# console_v2.net
KiCad netlist of a schematic drawn in EAGLE
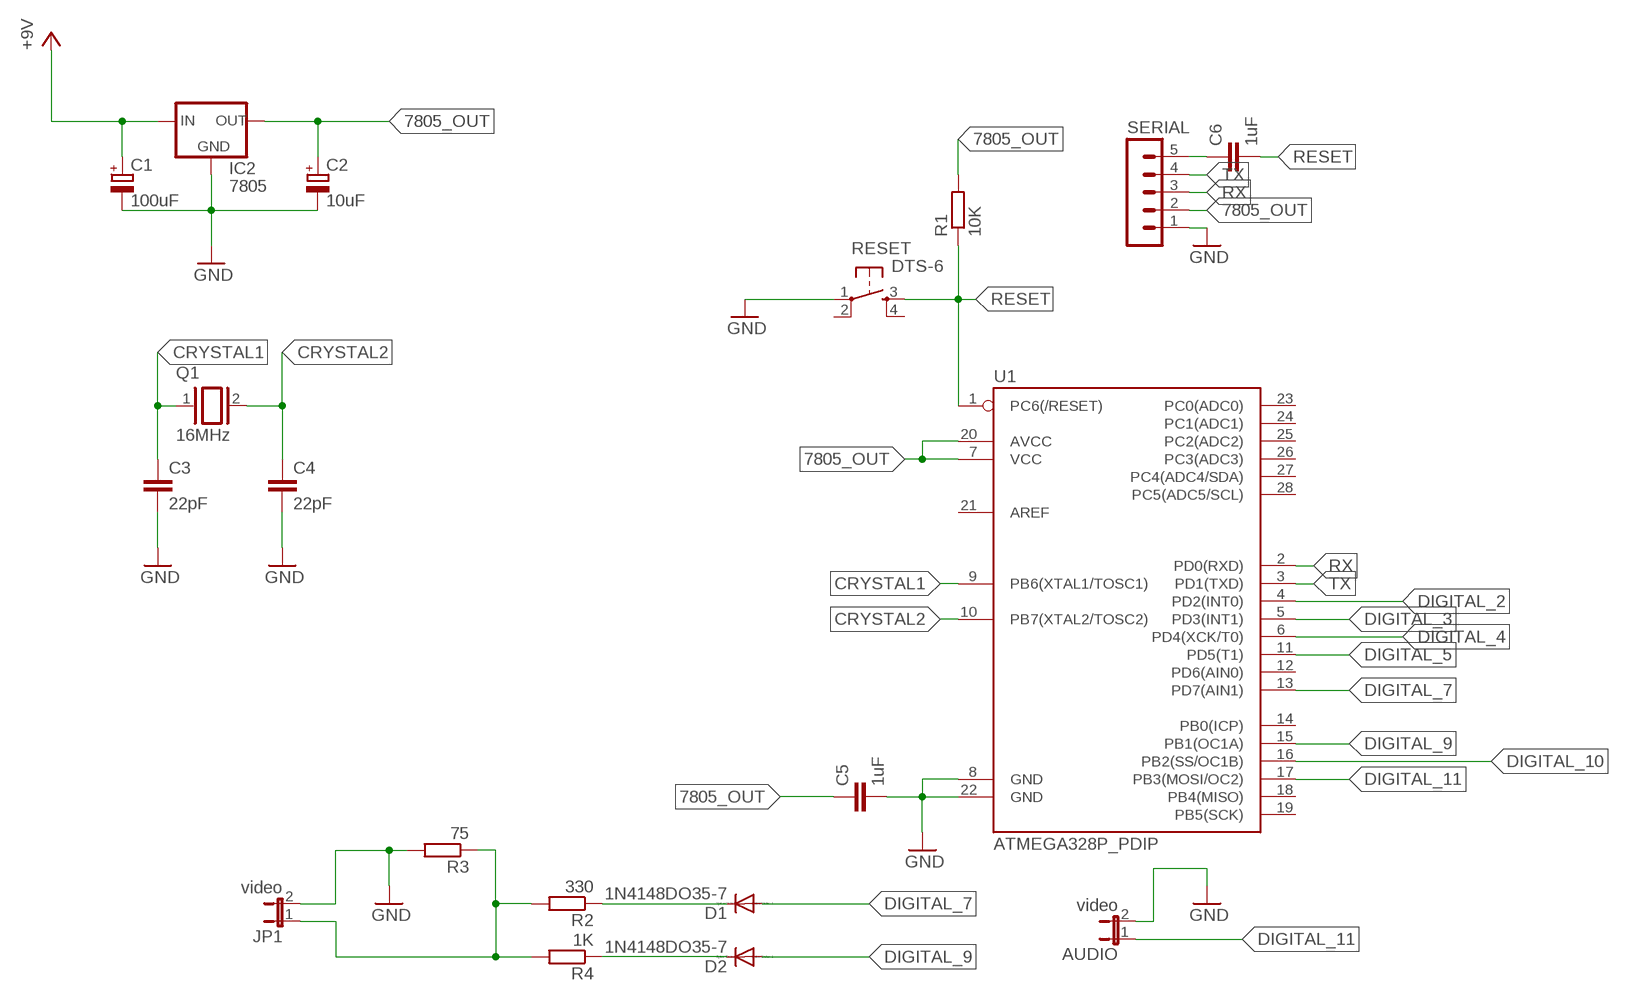
[diagram p0: schematic, sheet 1]

(export (version "E")
  (design (tool "Eeschema 10.0.6"))
  (components
    (comp (ref "AUDIO")
      (value "video")
      (footprint "eagle-import:JP1")
      (libsource (lib "eagle-import") (part "JP1E"))
    )
    (comp (ref "C1")
      (value "100uF")
      (footprint "eagle-import:E2,5-6E")
      (libsource (lib "eagle-import") (part "CPOL-EUE2,5-6E"))
    )
    (comp (ref "C2")
      (value "10uF")
      (footprint "eagle-import:E2,5-6E")
      (libsource (lib "eagle-import") (part "CPOL-EUE2,5-6E"))
    )
    (comp (ref "C3")
      (value "22pF")
      (footprint "eagle-import:C2.5-3")
      (libsource (lib "eagle-import") (part "C2,5-3"))
    )
    (comp (ref "C4")
      (value "22pF")
      (footprint "eagle-import:C2.5-3")
      (libsource (lib "eagle-import") (part "C2,5-3"))
    )
    (comp (ref "C5")
      (value "1uF")
      (footprint "eagle-import:C2.5-3")
      (libsource (lib "eagle-import") (part "C2,5-3"))
    )
    (comp (ref "C6")
      (value "1uF")
      (footprint "eagle-import:C2.5-3")
      (libsource (lib "eagle-import") (part "C2,5-3"))
    )
    (comp (ref "D1")
      (value "1N4148DO35-7")
      (footprint "eagle-import:DO35-7")
      (libsource (lib "eagle-import") (part "1N4148DO35-7"))
    )
    (comp (ref "D2")
      (value "1N4148DO35-7")
      (footprint "eagle-import:DO35-7")
      (libsource (lib "eagle-import") (part "1N4148DO35-7"))
    )
    (comp (ref "IC2")
      (value "7805")
      (footprint "eagle-import:78MXXL")
      (libsource (lib "eagle-import") (part "78MXXL"))
    )
    (comp (ref "JP1")
      (value "video")
      (footprint "eagle-import:JP1")
      (libsource (lib "eagle-import") (part "JP1E"))
    )
    (comp (ref "Q1")
      (value "16MHz")
      (footprint "eagle-import:QS")
      (libsource (lib "eagle-import") (part "XTAL/S"))
    )
    (comp (ref "R1")
      (value "10K")
      (footprint "eagle-import:0204_5")
      (libsource (lib "eagle-import") (part "R-EU_0204/5"))
    )
    (comp (ref "R2")
      (value "330")
      (footprint "eagle-import:0204_5")
      (libsource (lib "eagle-import") (part "R-EU_0204/5"))
    )
    (comp (ref "R3")
      (value "75")
      (footprint "eagle-import:0204_5")
      (libsource (lib "eagle-import") (part "R-EU_0204/5"))
    )
    (comp (ref "R4")
      (value "1K")
      (footprint "eagle-import:0204_5")
      (libsource (lib "eagle-import") (part "R-EU_0204/5"))
    )
    (comp (ref "RESET")
      (value "DTS-6")
      (footprint "eagle-import:DTS-6")
      (libsource (lib "eagle-import") (part "DTS-6"))
    )
    (comp (ref "SERIAL")
      (value "MA05-1")
      (footprint "eagle-import:MA05-1")
      (libsource (lib "eagle-import") (part "MA05-1"))
    )
    (comp (ref "U1")
      (value "ATMEGA328P_PDIP")
      (footprint "eagle-import:DIL28-3")
      (libsource (lib "eagle-import") (part "ATMEGA328P_PDIP"))
    )
  )
  (nets
    (net (code "1") (name "+9V") (class "Default")
      (node (ref "C1") (pin "+") (pinfunction "+_+") (pintype "passive"))
      (node (ref "IC2") (pin "IN") (pinfunction "IN_IN") (pintype "input"))
    )
    (net (code "2") (name "7805_OUT") (class "Default")
      (node (ref "C2") (pin "+") (pinfunction "+_+") (pintype "passive"))
      (node (ref "C5") (pin "1") (pinfunction "1_1") (pintype "passive"))
      (node (ref "IC2") (pin "OUT") (pinfunction "OUT_OUT") (pintype "passive"))
      (node (ref "R1") (pin "2") (pinfunction "2_2") (pintype "passive"))
      (node (ref "SERIAL") (pin "2") (pinfunction "2_2") (pintype "passive"))
      (node (ref "U1") (pin "20") (pinfunction "AVCC_20") (pintype "bidirectional"))
      (node (ref "U1") (pin "7") (pinfunction "VCC_7") (pintype "bidirectional"))
    )
    (net (code "3") (name "CRYSTAL1") (class "Default")
      (node (ref "C3") (pin "1") (pinfunction "1_1") (pintype "passive"))
      (node (ref "Q1") (pin "1") (pinfunction "1_1") (pintype "passive"))
      (node (ref "U1") (pin "9") (pinfunction "PB6(XTAL1/TOSC1)_9") (pintype "bidirectional"))
    )
    (net (code "4") (name "CRYSTAL2") (class "Default")
      (node (ref "C4") (pin "1") (pinfunction "1_1") (pintype "passive"))
      (node (ref "Q1") (pin "2") (pinfunction "2_2") (pintype "passive"))
      (node (ref "U1") (pin "10") (pinfunction "PB7(XTAL2/TOSC2)_10") (pintype "bidirectional"))
    )
    (net (code "5") (name "DIGITAL_2") (class "Default")
      (node (ref "U1") (pin "4") (pinfunction "PD2(INT0)_4") (pintype "bidirectional"))
    )
    (net (code "6") (name "DIGITAL_3") (class "Default")
      (node (ref "U1") (pin "5") (pinfunction "PD3(INT1)_5") (pintype "bidirectional"))
    )
    (net (code "7") (name "DIGITAL_4") (class "Default")
      (node (ref "U1") (pin "6") (pinfunction "PD4(XCK/T0)_6") (pintype "bidirectional"))
    )
    (net (code "8") (name "DIGITAL_5") (class "Default")
      (node (ref "U1") (pin "11") (pinfunction "PD5(T1)_11") (pintype "bidirectional"))
    )
    (net (code "9") (name "DIGITAL_7") (class "Default")
      (node (ref "D1") (pin "A") (pinfunction "A_A") (pintype "passive"))
      (node (ref "U1") (pin "13") (pinfunction "PD7(AIN1)_13") (pintype "bidirectional"))
    )
    (net (code "10") (name "DIGITAL_9") (class "Default")
      (node (ref "D2") (pin "A") (pinfunction "A_A") (pintype "passive"))
      (node (ref "U1") (pin "15") (pinfunction "PB1(OC1A)_15") (pintype "bidirectional"))
    )
    (net (code "11") (name "DIGITAL_10") (class "Default")
      (node (ref "U1") (pin "16") (pinfunction "PB2(SS/OC1B)_16") (pintype "bidirectional"))
    )
    (net (code "12") (name "DIGITAL_11") (class "Default")
      (node (ref "AUDIO") (pin "1") (pinfunction "1_1") (pintype "passive"))
      (node (ref "U1") (pin "17") (pinfunction "PB3(MOSI/OC2)_17") (pintype "bidirectional"))
    )
    (net (code "13") (name "GND") (class "Default")
      (node (ref "AUDIO") (pin "2") (pinfunction "2_2") (pintype "passive"))
      (node (ref "C1") (pin "-") (pinfunction "-_-") (pintype "passive"))
      (node (ref "C2") (pin "-") (pinfunction "-_-") (pintype "passive"))
      (node (ref "C3") (pin "2") (pinfunction "2_2") (pintype "passive"))
      (node (ref "C4") (pin "2") (pinfunction "2_2") (pintype "passive"))
      (node (ref "C5") (pin "2") (pinfunction "2_2") (pintype "passive"))
      (node (ref "IC2") (pin "GND") (pinfunction "GND_GND") (pintype "input"))
      (node (ref "JP1") (pin "2") (pinfunction "2_2") (pintype "passive"))
      (node (ref "R3") (pin "2") (pinfunction "2_2") (pintype "passive"))
      (node (ref "RESET") (pin "1") (pinfunction "1_1") (pintype "passive"))
      (node (ref "SERIAL") (pin "1") (pinfunction "1_1") (pintype "passive"))
      (node (ref "U1") (pin "22") (pinfunction "GND_22") (pintype "bidirectional"))
      (node (ref "U1") (pin "8") (pinfunction "GND_8") (pintype "bidirectional"))
    )
    (net (code "14") (name "Net-(C6-Pad1)") (class "Default")
      (node (ref "C6") (pin "1") (pinfunction "1_1") (pintype "passive"))
      (node (ref "SERIAL") (pin "5") (pinfunction "5_5") (pintype "passive"))
    )
    (net (code "15") (name "Net-(D1-PadC)") (class "Default")
      (node (ref "D1") (pin "C") (pinfunction "C_C") (pintype "passive"))
      (node (ref "R2") (pin "1") (pinfunction "1_1") (pintype "passive"))
    )
    (net (code "16") (name "Net-(D2-PadC)") (class "Default")
      (node (ref "D2") (pin "C") (pinfunction "C_C") (pintype "passive"))
      (node (ref "R4") (pin "1") (pinfunction "1_1") (pintype "passive"))
    )
    (net (code "17") (name "Net-(JP1-Pad1)") (class "Default")
      (node (ref "JP1") (pin "1") (pinfunction "1_1") (pintype "passive"))
      (node (ref "R2") (pin "2") (pinfunction "2_2") (pintype "passive"))
      (node (ref "R3") (pin "1") (pinfunction "1_1") (pintype "passive"))
      (node (ref "R4") (pin "2") (pinfunction "2_2") (pintype "passive"))
    )
    (net (code "18") (name "RESET") (class "Default")
      (node (ref "C6") (pin "2") (pinfunction "2_2") (pintype "passive"))
      (node (ref "R1") (pin "1") (pinfunction "1_1") (pintype "passive"))
      (node (ref "RESET") (pin "3") (pinfunction "3_3") (pintype "passive"))
      (node (ref "U1") (pin "1") (pinfunction "PC6(/RESET)_1") (pintype "bidirectional"))
    )
    (net (code "19") (name "RX") (class "Default")
      (node (ref "SERIAL") (pin "3") (pinfunction "3_3") (pintype "passive"))
      (node (ref "U1") (pin "2") (pinfunction "PD0(RXD)_2") (pintype "bidirectional"))
    )
    (net (code "20") (name "TX") (class "Default")
      (node (ref "SERIAL") (pin "4") (pinfunction "4_4") (pintype "passive"))
      (node (ref "U1") (pin "3") (pinfunction "PD1(TXD)_3") (pintype "bidirectional"))
    )
    (net (code "21") (name "unconnected-(RESET-Pad2)") (class "Default")
      (node (ref "RESET") (pin "2") (pinfunction "2_2") (pintype "passive"))
    )
    (net (code "22") (name "unconnected-(RESET-Pad4)") (class "Default")
      (node (ref "RESET") (pin "4") (pinfunction "4_4") (pintype "passive"))
    )
    (net (code "23") (name "unconnected-(U1-AREF-Pad21)") (class "Default")
      (node (ref "U1") (pin "21") (pinfunction "AREF_21") (pintype "bidirectional"))
    )
    (net (code "24") (name "unconnected-(U1-PB0(ICP)-Pad14)") (class "Default")
      (node (ref "U1") (pin "14") (pinfunction "PB0(ICP)_14") (pintype "bidirectional"))
    )
    (net (code "25") (name "unconnected-(U1-PB4(MISO)-Pad18)") (class "Default")
      (node (ref "U1") (pin "18") (pinfunction "PB4(MISO)_18") (pintype "bidirectional"))
    )
    (net (code "26") (name "unconnected-(U1-PB5(SCK)-Pad19)") (class "Default")
      (node (ref "U1") (pin "19") (pinfunction "PB5(SCK)_19") (pintype "bidirectional"))
    )
    (net (code "27") (name "unconnected-(U1-PC0(ADC0)-Pad23)") (class "Default")
      (node (ref "U1") (pin "23") (pinfunction "PC0(ADC0)_23") (pintype "bidirectional"))
    )
    (net (code "28") (name "unconnected-(U1-PC1(ADC1)-Pad24)") (class "Default")
      (node (ref "U1") (pin "24") (pinfunction "PC1(ADC1)_24") (pintype "bidirectional"))
    )
    (net (code "29") (name "unconnected-(U1-PC2(ADC2)-Pad25)") (class "Default")
      (node (ref "U1") (pin "25") (pinfunction "PC2(ADC2)_25") (pintype "bidirectional"))
    )
    (net (code "30") (name "unconnected-(U1-PC3(ADC3)-Pad26)") (class "Default")
      (node (ref "U1") (pin "26") (pinfunction "PC3(ADC3)_26") (pintype "bidirectional"))
    )
    (net (code "31") (name "unconnected-(U1-PC4(ADC4{slash}SDA)-Pad27)") (class "Default")
      (node (ref "U1") (pin "27") (pinfunction "PC4(ADC4/SDA)_27") (pintype "bidirectional"))
    )
    (net (code "32") (name "unconnected-(U1-PC5(ADC5{slash}SCL)-Pad28)") (class "Default")
      (node (ref "U1") (pin "28") (pinfunction "PC5(ADC5/SCL)_28") (pintype "bidirectional"))
    )
    (net (code "33") (name "unconnected-(U1-PD6(AIN0)-Pad12)") (class "Default")
      (node (ref "U1") (pin "12") (pinfunction "PD6(AIN0)_12") (pintype "bidirectional"))
    )
  )
)
